# B105X.net
KiCad netlist of a schematic drawn in EAGLE
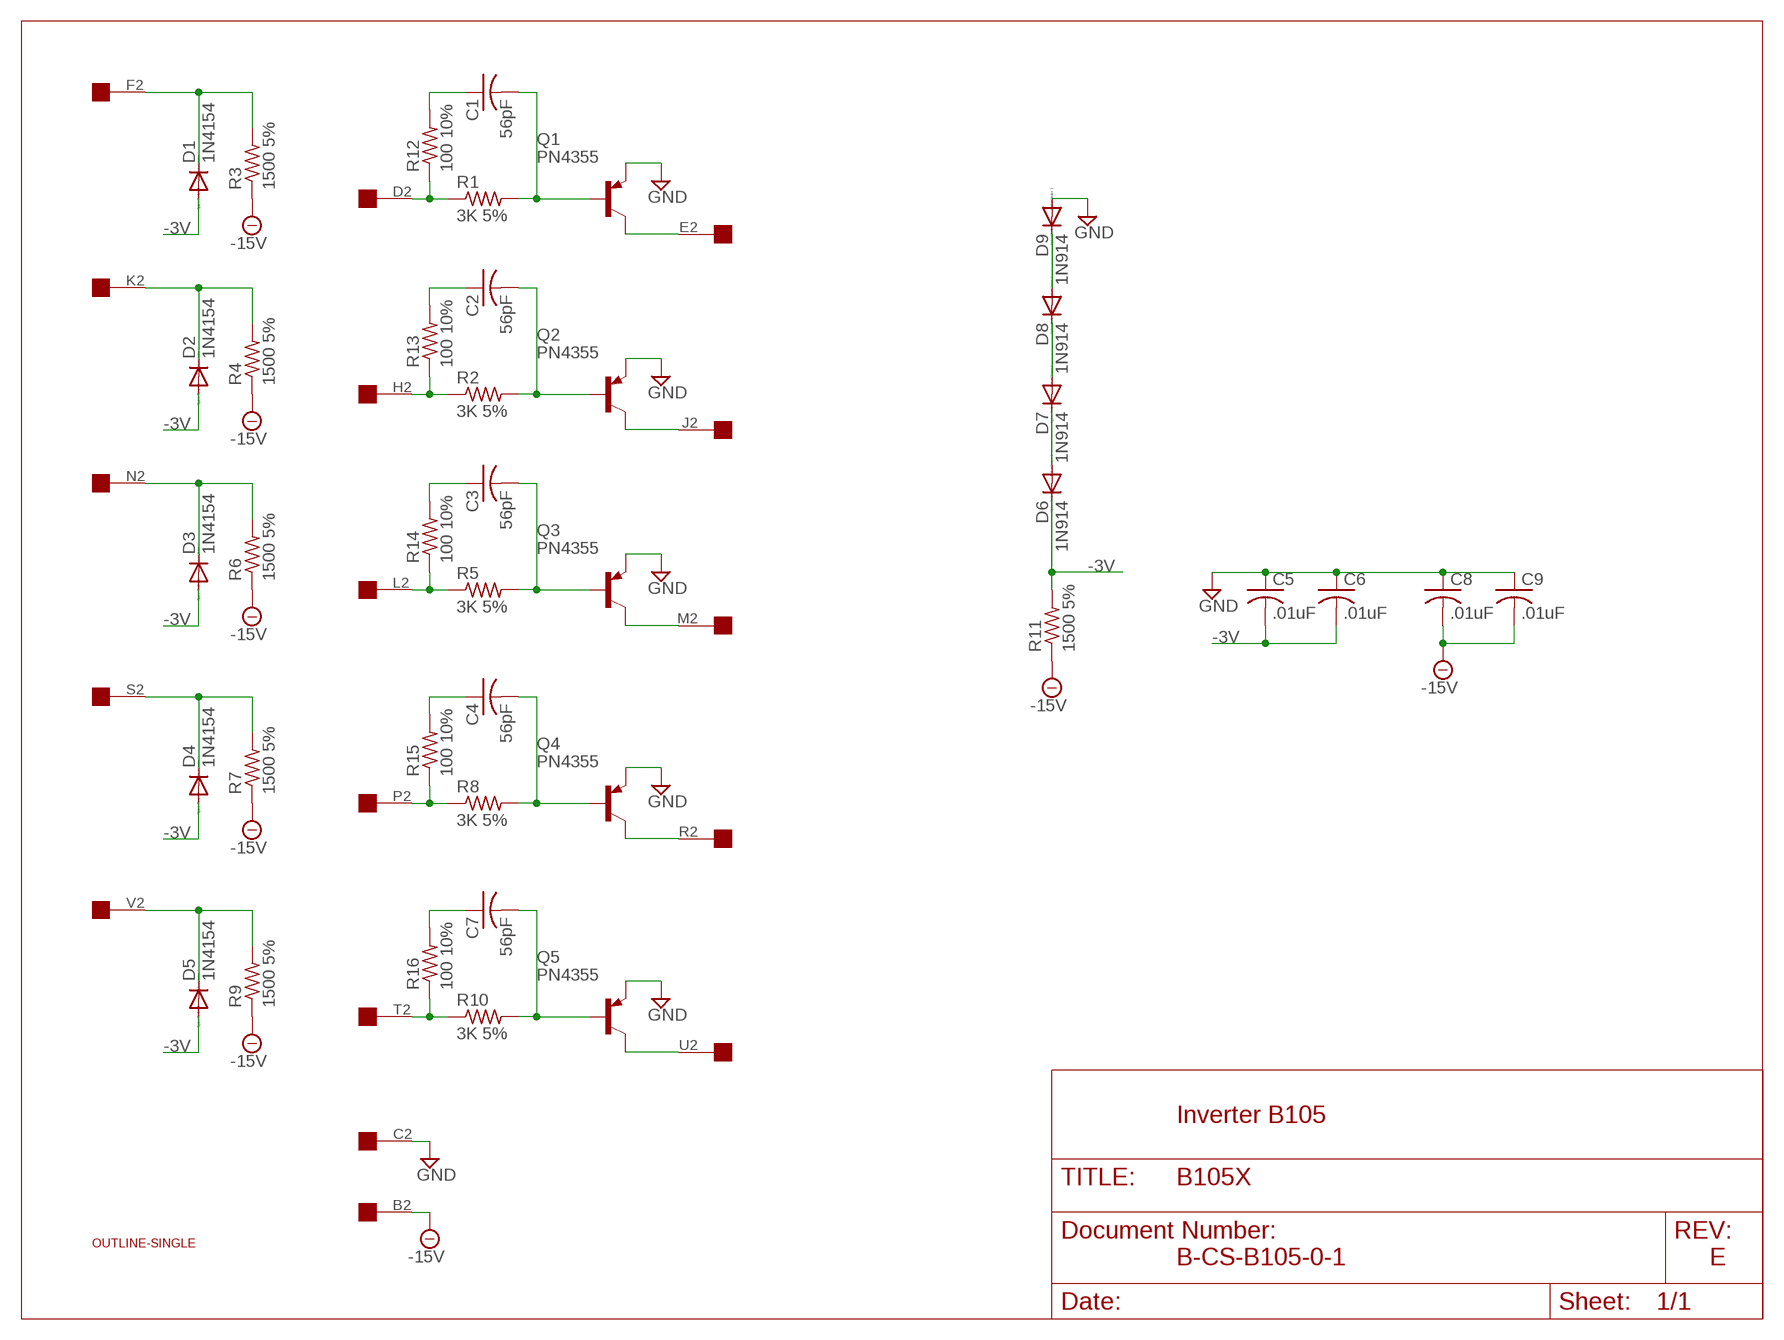
[diagram p0: schematic, sheet 1]

(export (version "E")
  (design (tool "Eeschema 10.0.6"))
  (components
    (comp (ref "C1")
      (value "56pF")
      (footprint "eagle-import:C102-043X133")
      (libsource (lib "eagle-import") (part "C-US102-043X133"))
    )
    (comp (ref "C2")
      (value "56pF")
      (footprint "eagle-import:C102-043X133")
      (libsource (lib "eagle-import") (part "C-US102-043X133"))
    )
    (comp (ref "C3")
      (value "56pF")
      (footprint "eagle-import:C102-043X133")
      (libsource (lib "eagle-import") (part "C-US102-043X133"))
    )
    (comp (ref "C4")
      (value "56pF")
      (footprint "eagle-import:C102-043X133")
      (libsource (lib "eagle-import") (part "C-US102-043X133"))
    )
    (comp (ref "C5")
      (value ".01uF")
      (footprint "eagle-import:C102-043X133")
      (libsource (lib "eagle-import") (part "C-US102-043X133"))
    )
    (comp (ref "C6")
      (value ".01uF")
      (footprint "eagle-import:C102-043X133")
      (libsource (lib "eagle-import") (part "C-US102-043X133"))
    )
    (comp (ref "C7")
      (value "56pF")
      (footprint "eagle-import:C102-043X133")
      (libsource (lib "eagle-import") (part "C-US102-043X133"))
    )
    (comp (ref "C8")
      (value ".01uF")
      (footprint "eagle-import:C102-043X133")
      (libsource (lib "eagle-import") (part "C-US102-043X133"))
    )
    (comp (ref "C9")
      (value ".01uF")
      (footprint "eagle-import:C102-043X133")
      (libsource (lib "eagle-import") (part "C-US102-043X133"))
    )
    (comp (ref "D1")
      (value "1N4154")
      (footprint "eagle-import:DO35-10")
      (libsource (lib "eagle-import") (part "1N4148DO35-10"))
    )
    (comp (ref "D2")
      (value "1N4154")
      (footprint "eagle-import:DO35-10")
      (libsource (lib "eagle-import") (part "1N4148DO35-10"))
    )
    (comp (ref "D3")
      (value "1N4154")
      (footprint "eagle-import:DO35-10")
      (libsource (lib "eagle-import") (part "1N4148DO35-10"))
    )
    (comp (ref "D4")
      (value "1N4154")
      (footprint "eagle-import:DO35-10")
      (libsource (lib "eagle-import") (part "1N4148DO35-10"))
    )
    (comp (ref "D5")
      (value "1N4154")
      (footprint "eagle-import:DO35-10")
      (libsource (lib "eagle-import") (part "1N4148DO35-10"))
    )
    (comp (ref "D6")
      (value "1N914")
      (footprint "eagle-import:DO35-10")
      (libsource (lib "eagle-import") (part "1N4148DO35-10"))
    )
    (comp (ref "D7")
      (value "1N914")
      (footprint "eagle-import:DO35-10")
      (libsource (lib "eagle-import") (part "1N4148DO35-10"))
    )
    (comp (ref "D8")
      (value "1N914")
      (footprint "eagle-import:DO35-10")
      (libsource (lib "eagle-import") (part "1N4148DO35-10"))
    )
    (comp (ref "D9")
      (value "1N914")
      (footprint "eagle-import:DO35-10")
      (libsource (lib "eagle-import") (part "1N4148DO35-10"))
    )
    (comp (ref "Q1")
      (value "PN4355")
      (footprint "eagle-import:TO39")
      (libsource (lib "eagle-import") (part "2N2904"))
    )
    (comp (ref "Q2")
      (value "PN4355")
      (footprint "eagle-import:TO39")
      (libsource (lib "eagle-import") (part "2N2904"))
    )
    (comp (ref "Q3")
      (value "PN4355")
      (footprint "eagle-import:TO39")
      (libsource (lib "eagle-import") (part "2N2904"))
    )
    (comp (ref "Q4")
      (value "PN4355")
      (footprint "eagle-import:TO39")
      (libsource (lib "eagle-import") (part "2N2904"))
    )
    (comp (ref "Q5")
      (value "PN4355")
      (footprint "eagle-import:TO39")
      (libsource (lib "eagle-import") (part "2N2904"))
    )
    (comp (ref "R1")
      (value "3K 5%")
      (footprint "eagle-import:0207_10")
      (libsource (lib "eagle-import") (part "R-US_0207/10"))
    )
    (comp (ref "R2")
      (value "3K 5%")
      (footprint "eagle-import:0207_10")
      (libsource (lib "eagle-import") (part "R-US_0207/10"))
    )
    (comp (ref "R3")
      (value "1500 5%")
      (footprint "eagle-import:0207_10")
      (libsource (lib "eagle-import") (part "R-US_0207/10"))
    )
    (comp (ref "R4")
      (value "1500 5%")
      (footprint "eagle-import:0207_10")
      (libsource (lib "eagle-import") (part "R-US_0207/10"))
    )
    (comp (ref "R5")
      (value "3K 5%")
      (footprint "eagle-import:0207_10")
      (libsource (lib "eagle-import") (part "R-US_0207/10"))
    )
    (comp (ref "R6")
      (value "1500 5%")
      (footprint "eagle-import:0207_10")
      (libsource (lib "eagle-import") (part "R-US_0207/10"))
    )
    (comp (ref "R7")
      (value "1500 5%")
      (footprint "eagle-import:0207_10")
      (libsource (lib "eagle-import") (part "R-US_0207/10"))
    )
    (comp (ref "R8")
      (value "3K 5%")
      (footprint "eagle-import:0207_10")
      (libsource (lib "eagle-import") (part "R-US_0207/10"))
    )
    (comp (ref "R9")
      (value "1500 5%")
      (footprint "eagle-import:0207_10")
      (libsource (lib "eagle-import") (part "R-US_0207/10"))
    )
    (comp (ref "R10")
      (value "3K 5%")
      (footprint "eagle-import:0207_10")
      (libsource (lib "eagle-import") (part "R-US_0207/10"))
    )
    (comp (ref "R11")
      (value "1500 5%")
      (footprint "eagle-import:0207_10")
      (libsource (lib "eagle-import") (part "R-US_0207/10"))
    )
    (comp (ref "R12")
      (value "100 10%")
      (footprint "eagle-import:0207_10")
      (libsource (lib "eagle-import") (part "R-US_0207/10"))
    )
    (comp (ref "R13")
      (value "100 10%")
      (footprint "eagle-import:0207_10")
      (libsource (lib "eagle-import") (part "R-US_0207/10"))
    )
    (comp (ref "R14")
      (value "100 10%")
      (footprint "eagle-import:0207_10")
      (libsource (lib "eagle-import") (part "R-US_0207/10"))
    )
    (comp (ref "R15")
      (value "100 10%")
      (footprint "eagle-import:0207_10")
      (libsource (lib "eagle-import") (part "R-US_0207/10"))
    )
    (comp (ref "R16")
      (value "100 10%")
      (footprint "eagle-import:0207_10")
      (libsource (lib "eagle-import") (part "R-US_0207/10"))
    )
    (comp (ref "U$1")
      (value "OUTLINE-SINGLE")
      (footprint "eagle-import:SINGLE")
      (libsource (lib "eagle-import") (part "OUTLINE-SINGLE"))
    )
    (comp (ref "U$2")
      (value "EDGE-1")
      (footprint "eagle-import:EDGE-CON1")
      (libsource (lib "eagle-import") (part "EDGE-1"))
    )
  )
  (nets
    (net (code "1") (name "-15V") (class "Default")
      (node (ref "C8") (pin "2") (pinfunction "2_2") (pintype "passive"))
      (node (ref "C9") (pin "2") (pinfunction "2_2") (pintype "passive"))
      (node (ref "R11") (pin "1") (pinfunction "1_1") (pintype "passive"))
      (node (ref "R3") (pin "1") (pinfunction "1_1") (pintype "passive"))
      (node (ref "R4") (pin "1") (pinfunction "1_1") (pintype "passive"))
      (node (ref "R6") (pin "1") (pinfunction "1_1") (pintype "passive"))
      (node (ref "R7") (pin "1") (pinfunction "1_1") (pintype "passive"))
      (node (ref "R9") (pin "1") (pinfunction "1_1") (pintype "passive"))
      (node (ref "U$2") (pin "B2") (pinfunction "1_B2") (pintype "bidirectional"))
    )
    (net (code "2") (name "/-3V") (class "Default")
      (node (ref "C5") (pin "2") (pinfunction "2_2") (pintype "passive"))
      (node (ref "C6") (pin "2") (pinfunction "2_2") (pintype "passive"))
      (node (ref "D1") (pin "A") (pinfunction "A_A") (pintype "passive"))
      (node (ref "D2") (pin "A") (pinfunction "A_A") (pintype "passive"))
      (node (ref "D3") (pin "A") (pinfunction "A_A") (pintype "passive"))
      (node (ref "D4") (pin "A") (pinfunction "A_A") (pintype "passive"))
      (node (ref "D5") (pin "A") (pinfunction "A_A") (pintype "passive"))
      (node (ref "D6") (pin "C") (pinfunction "C_C") (pintype "passive"))
      (node (ref "R11") (pin "2") (pinfunction "2_2") (pintype "passive"))
    )
    (net (code "3") (name "GND") (class "Default")
      (node (ref "C5") (pin "1") (pinfunction "1_1") (pintype "passive"))
      (node (ref "C6") (pin "1") (pinfunction "1_1") (pintype "passive"))
      (node (ref "C8") (pin "1") (pinfunction "1_1") (pintype "passive"))
      (node (ref "C9") (pin "1") (pinfunction "1_1") (pintype "passive"))
      (node (ref "D9") (pin "A") (pinfunction "A_A") (pintype "passive"))
      (node (ref "Q1") (pin "1") (pinfunction "E_1") (pintype "passive"))
      (node (ref "Q2") (pin "1") (pinfunction "E_1") (pintype "passive"))
      (node (ref "Q3") (pin "1") (pinfunction "E_1") (pintype "passive"))
      (node (ref "Q4") (pin "1") (pinfunction "E_1") (pintype "passive"))
      (node (ref "Q5") (pin "1") (pinfunction "E_1") (pintype "passive"))
      (node (ref "U$2") (pin "C2") (pinfunction "1_C2") (pintype "bidirectional"))
    )
    (net (code "4") (name "Net-(C1-Pad1)") (class "Default")
      (node (ref "C1") (pin "1") (pinfunction "1_1") (pintype "passive"))
      (node (ref "R12") (pin "2") (pinfunction "2_2") (pintype "passive"))
    )
    (net (code "5") (name "Net-(C2-Pad1)") (class "Default")
      (node (ref "C2") (pin "1") (pinfunction "1_1") (pintype "passive"))
      (node (ref "R13") (pin "2") (pinfunction "2_2") (pintype "passive"))
    )
    (net (code "6") (name "Net-(C3-Pad1)") (class "Default")
      (node (ref "C3") (pin "1") (pinfunction "1_1") (pintype "passive"))
      (node (ref "R14") (pin "2") (pinfunction "2_2") (pintype "passive"))
    )
    (net (code "7") (name "Net-(C4-Pad1)") (class "Default")
      (node (ref "C4") (pin "1") (pinfunction "1_1") (pintype "passive"))
      (node (ref "R15") (pin "2") (pinfunction "2_2") (pintype "passive"))
    )
    (net (code "8") (name "Net-(C7-Pad1)") (class "Default")
      (node (ref "C7") (pin "1") (pinfunction "1_1") (pintype "passive"))
      (node (ref "R16") (pin "2") (pinfunction "2_2") (pintype "passive"))
    )
    (net (code "9") (name "Net-(D6-PadA)") (class "Default")
      (node (ref "D6") (pin "A") (pinfunction "A_A") (pintype "passive"))
      (node (ref "D7") (pin "C") (pinfunction "C_C") (pintype "passive"))
    )
    (net (code "10") (name "Net-(D7-PadA)") (class "Default")
      (node (ref "D7") (pin "A") (pinfunction "A_A") (pintype "passive"))
      (node (ref "D8") (pin "C") (pinfunction "C_C") (pintype "passive"))
    )
    (net (code "11") (name "Net-(D8-PadA)") (class "Default")
      (node (ref "D8") (pin "A") (pinfunction "A_A") (pintype "passive"))
      (node (ref "D9") (pin "C") (pinfunction "C_C") (pintype "passive"))
    )
    (net (code "12") (name "Net-(Q1-B)") (class "Default")
      (node (ref "C1") (pin "2") (pinfunction "2_2") (pintype "passive"))
      (node (ref "Q1") (pin "2") (pinfunction "B_2") (pintype "passive"))
      (node (ref "R1") (pin "2") (pinfunction "2_2") (pintype "passive"))
    )
    (net (code "13") (name "Net-(Q1-C)") (class "Default")
      (node (ref "Q1") (pin "3") (pinfunction "C_3") (pintype "passive"))
      (node (ref "U$2") (pin "E2") (pinfunction "1_E2") (pintype "bidirectional"))
    )
    (net (code "14") (name "Net-(Q2-B)") (class "Default")
      (node (ref "C2") (pin "2") (pinfunction "2_2") (pintype "passive"))
      (node (ref "Q2") (pin "2") (pinfunction "B_2") (pintype "passive"))
      (node (ref "R2") (pin "2") (pinfunction "2_2") (pintype "passive"))
    )
    (net (code "15") (name "Net-(Q2-C)") (class "Default")
      (node (ref "Q2") (pin "3") (pinfunction "C_3") (pintype "passive"))
      (node (ref "U$2") (pin "J2") (pinfunction "1_J2") (pintype "bidirectional"))
    )
    (net (code "16") (name "Net-(Q3-B)") (class "Default")
      (node (ref "C3") (pin "2") (pinfunction "2_2") (pintype "passive"))
      (node (ref "Q3") (pin "2") (pinfunction "B_2") (pintype "passive"))
      (node (ref "R5") (pin "2") (pinfunction "2_2") (pintype "passive"))
    )
    (net (code "17") (name "Net-(Q3-C)") (class "Default")
      (node (ref "Q3") (pin "3") (pinfunction "C_3") (pintype "passive"))
      (node (ref "U$2") (pin "M2") (pinfunction "1_M2") (pintype "bidirectional"))
    )
    (net (code "18") (name "Net-(Q4-B)") (class "Default")
      (node (ref "C4") (pin "2") (pinfunction "2_2") (pintype "passive"))
      (node (ref "Q4") (pin "2") (pinfunction "B_2") (pintype "passive"))
      (node (ref "R8") (pin "2") (pinfunction "2_2") (pintype "passive"))
    )
    (net (code "19") (name "Net-(Q4-C)") (class "Default")
      (node (ref "Q4") (pin "3") (pinfunction "C_3") (pintype "passive"))
      (node (ref "U$2") (pin "R2") (pinfunction "1_R2") (pintype "bidirectional"))
    )
    (net (code "20") (name "Net-(Q5-B)") (class "Default")
      (node (ref "C7") (pin "2") (pinfunction "2_2") (pintype "passive"))
      (node (ref "Q5") (pin "2") (pinfunction "B_2") (pintype "passive"))
      (node (ref "R10") (pin "2") (pinfunction "2_2") (pintype "passive"))
    )
    (net (code "21") (name "Net-(Q5-C)") (class "Default")
      (node (ref "Q5") (pin "3") (pinfunction "C_3") (pintype "passive"))
      (node (ref "U$2") (pin "U2") (pinfunction "1_U2") (pintype "bidirectional"))
    )
    (net (code "22") (name "Net-(U$2D-1)") (class "Default")
      (node (ref "R1") (pin "1") (pinfunction "1_1") (pintype "passive"))
      (node (ref "R12") (pin "1") (pinfunction "1_1") (pintype "passive"))
      (node (ref "U$2") (pin "D2") (pinfunction "1_D2") (pintype "bidirectional"))
    )
    (net (code "23") (name "Net-(U$2F-1)") (class "Default")
      (node (ref "D1") (pin "C") (pinfunction "C_C") (pintype "passive"))
      (node (ref "R3") (pin "2") (pinfunction "2_2") (pintype "passive"))
      (node (ref "U$2") (pin "F2") (pinfunction "1_F2") (pintype "bidirectional"))
    )
    (net (code "24") (name "Net-(U$2G-1)") (class "Default")
      (node (ref "R13") (pin "1") (pinfunction "1_1") (pintype "passive"))
      (node (ref "R2") (pin "1") (pinfunction "1_1") (pintype "passive"))
      (node (ref "U$2") (pin "H2") (pinfunction "1_H2") (pintype "bidirectional"))
    )
    (net (code "25") (name "Net-(U$2I-1)") (class "Default")
      (node (ref "D2") (pin "C") (pinfunction "C_C") (pintype "passive"))
      (node (ref "R4") (pin "2") (pinfunction "2_2") (pintype "passive"))
      (node (ref "U$2") (pin "K2") (pinfunction "1_K2") (pintype "bidirectional"))
    )
    (net (code "26") (name "Net-(U$2J-1)") (class "Default")
      (node (ref "R14") (pin "1") (pinfunction "1_1") (pintype "passive"))
      (node (ref "R5") (pin "1") (pinfunction "1_1") (pintype "passive"))
      (node (ref "U$2") (pin "L2") (pinfunction "1_L2") (pintype "bidirectional"))
    )
    (net (code "27") (name "Net-(U$2L-1)") (class "Default")
      (node (ref "D3") (pin "C") (pinfunction "C_C") (pintype "passive"))
      (node (ref "R6") (pin "2") (pinfunction "2_2") (pintype "passive"))
      (node (ref "U$2") (pin "N2") (pinfunction "1_N2") (pintype "bidirectional"))
    )
    (net (code "28") (name "Net-(U$2M-1)") (class "Default")
      (node (ref "R15") (pin "1") (pinfunction "1_1") (pintype "passive"))
      (node (ref "R8") (pin "1") (pinfunction "1_1") (pintype "passive"))
      (node (ref "U$2") (pin "P2") (pinfunction "1_P2") (pintype "bidirectional"))
    )
    (net (code "29") (name "Net-(U$2O-1)") (class "Default")
      (node (ref "D4") (pin "C") (pinfunction "C_C") (pintype "passive"))
      (node (ref "R7") (pin "2") (pinfunction "2_2") (pintype "passive"))
      (node (ref "U$2") (pin "S2") (pinfunction "1_S2") (pintype "bidirectional"))
    )
    (net (code "30") (name "Net-(U$2P-1)") (class "Default")
      (node (ref "R10") (pin "1") (pinfunction "1_1") (pintype "passive"))
      (node (ref "R16") (pin "1") (pinfunction "1_1") (pintype "passive"))
      (node (ref "U$2") (pin "T2") (pinfunction "1_T2") (pintype "bidirectional"))
    )
    (net (code "31") (name "Net-(U$2R-1)") (class "Default")
      (node (ref "D5") (pin "C") (pinfunction "C_C") (pintype "passive"))
      (node (ref "R9") (pin "2") (pinfunction "2_2") (pintype "passive"))
      (node (ref "U$2") (pin "V2") (pinfunction "1_V2") (pintype "bidirectional"))
    )
  )
)
